# B115C.net
KiCad netlist of a schematic drawn in EAGLE
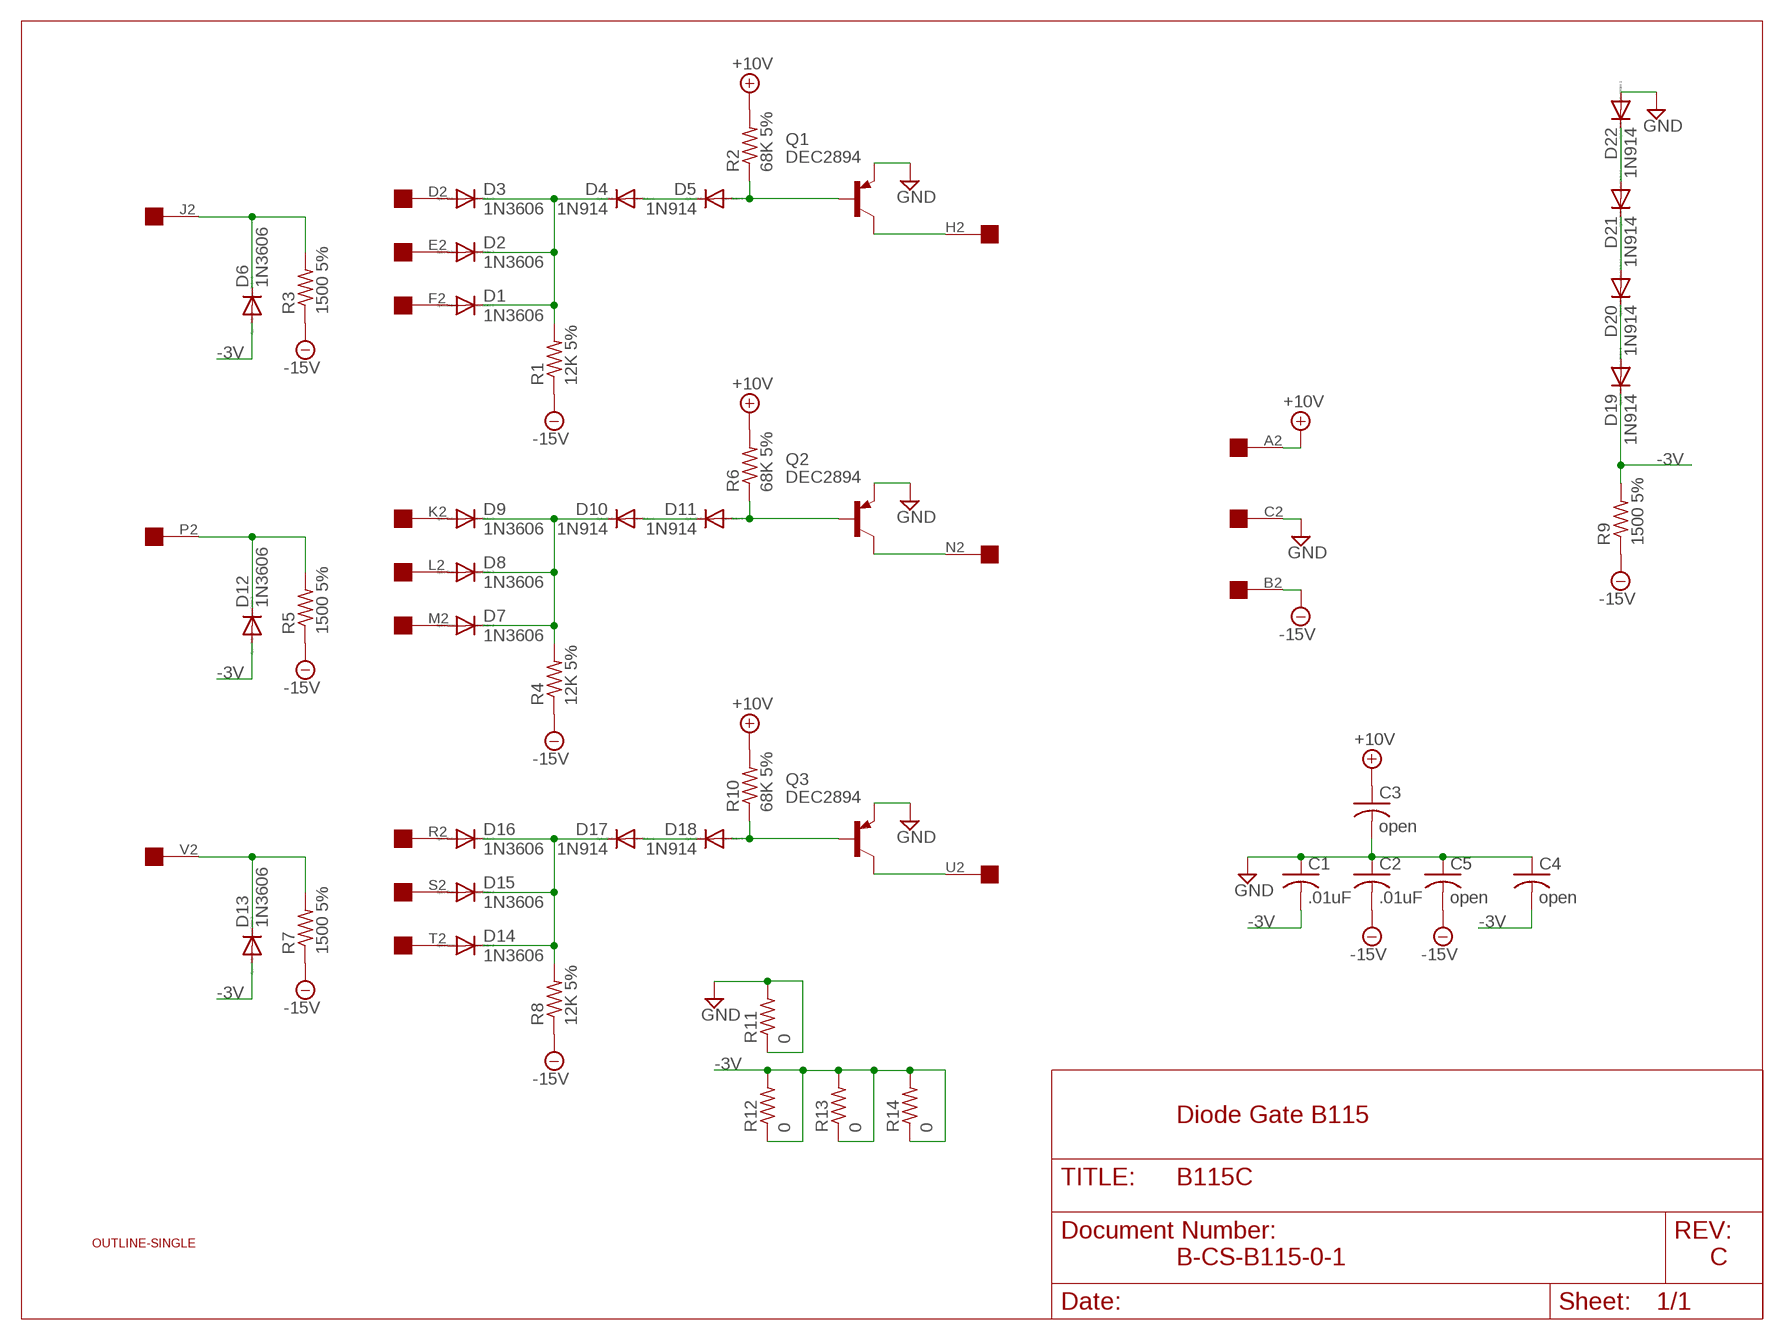
[diagram p0: schematic, sheet 1]

(export (version "E")
  (design (tool "Eeschema 10.0.6"))
  (components
    (comp (ref "C1")
      (value ".01uF")
      (footprint "eagle-import:C063-025X075")
      (libsource (lib "eagle-import") (part "C-US"))
    )
    (comp (ref "C2")
      (value ".01uF")
      (footprint "eagle-import:C063-025X075")
      (libsource (lib "eagle-import") (part "C-US"))
    )
    (comp (ref "C3")
      (value "open")
      (footprint "eagle-import:C063-025X075")
      (libsource (lib "eagle-import") (part "C-US"))
    )
    (comp (ref "C4")
      (value "open")
      (footprint "eagle-import:C063-025X075")
      (libsource (lib "eagle-import") (part "C-US"))
    )
    (comp (ref "C5")
      (value "open")
      (footprint "eagle-import:C063-025X075")
      (libsource (lib "eagle-import") (part "C-US"))
    )
    (comp (ref "D1")
      (value "1N3606")
      (footprint "eagle-import:DO35-10")
      (libsource (lib "eagle-import") (part "1N4148DO35-10"))
    )
    (comp (ref "D2")
      (value "1N3606")
      (footprint "eagle-import:DO35-10")
      (libsource (lib "eagle-import") (part "1N4148DO35-10"))
    )
    (comp (ref "D3")
      (value "1N3606")
      (footprint "eagle-import:DO35-10")
      (libsource (lib "eagle-import") (part "1N4148DO35-10"))
    )
    (comp (ref "D4")
      (value "1N914")
      (footprint "eagle-import:DO35-10")
      (libsource (lib "eagle-import") (part "1N4148DO35-10"))
    )
    (comp (ref "D5")
      (value "1N914")
      (footprint "eagle-import:DO35-10")
      (libsource (lib "eagle-import") (part "1N4148DO35-10"))
    )
    (comp (ref "D6")
      (value "1N3606")
      (footprint "eagle-import:DO35-10")
      (libsource (lib "eagle-import") (part "1N4148DO35-10"))
    )
    (comp (ref "D7")
      (value "1N3606")
      (footprint "eagle-import:DO35-10")
      (libsource (lib "eagle-import") (part "1N4148DO35-10"))
    )
    (comp (ref "D8")
      (value "1N3606")
      (footprint "eagle-import:DO35-10")
      (libsource (lib "eagle-import") (part "1N4148DO35-10"))
    )
    (comp (ref "D9")
      (value "1N3606")
      (footprint "eagle-import:DO35-10")
      (libsource (lib "eagle-import") (part "1N4148DO35-10"))
    )
    (comp (ref "D10")
      (value "1N914")
      (footprint "eagle-import:DO35-10")
      (libsource (lib "eagle-import") (part "1N4148DO35-10"))
    )
    (comp (ref "D11")
      (value "1N914")
      (footprint "eagle-import:DO35-10")
      (libsource (lib "eagle-import") (part "1N4148DO35-10"))
    )
    (comp (ref "D12")
      (value "1N3606")
      (footprint "eagle-import:DO35-10")
      (libsource (lib "eagle-import") (part "1N4148DO35-10"))
    )
    (comp (ref "D13")
      (value "1N3606")
      (footprint "eagle-import:DO35-10")
      (libsource (lib "eagle-import") (part "1N4148DO35-10"))
    )
    (comp (ref "D14")
      (value "1N3606")
      (footprint "eagle-import:DO35-10")
      (libsource (lib "eagle-import") (part "1N4148DO35-10"))
    )
    (comp (ref "D15")
      (value "1N3606")
      (footprint "eagle-import:DO35-10")
      (libsource (lib "eagle-import") (part "1N4148DO35-10"))
    )
    (comp (ref "D16")
      (value "1N3606")
      (footprint "eagle-import:DO35-10")
      (libsource (lib "eagle-import") (part "1N4148DO35-10"))
    )
    (comp (ref "D17")
      (value "1N914")
      (footprint "eagle-import:DO35-10")
      (libsource (lib "eagle-import") (part "1N4148DO35-10"))
    )
    (comp (ref "D18")
      (value "1N914")
      (footprint "eagle-import:DO35-10")
      (libsource (lib "eagle-import") (part "1N4148DO35-10"))
    )
    (comp (ref "D19")
      (value "1N914")
      (footprint "eagle-import:DO35-10")
      (libsource (lib "eagle-import") (part "1N4148DO35-10"))
    )
    (comp (ref "D20")
      (value "1N914")
      (footprint "eagle-import:DO35-10")
      (libsource (lib "eagle-import") (part "1N4148DO35-10"))
    )
    (comp (ref "D21")
      (value "1N914")
      (footprint "eagle-import:DO35-10")
      (libsource (lib "eagle-import") (part "1N4148DO35-10"))
    )
    (comp (ref "D22")
      (value "1N914")
      (footprint "eagle-import:DO35-10")
      (libsource (lib "eagle-import") (part "1N4148DO35-10"))
    )
    (comp (ref "Q1")
      (value "DEC2894")
      (footprint "eagle-import:TO39")
      (libsource (lib "eagle-import") (part "2N2904"))
    )
    (comp (ref "Q2")
      (value "DEC2894")
      (footprint "eagle-import:TO39")
      (libsource (lib "eagle-import") (part "2N2904"))
    )
    (comp (ref "Q3")
      (value "DEC2894")
      (footprint "eagle-import:TO39")
      (libsource (lib "eagle-import") (part "2N2904"))
    )
    (comp (ref "R1")
      (value "12K 5%")
      (footprint "eagle-import:0207_10")
      (libsource (lib "eagle-import") (part "R-US_0207/10"))
    )
    (comp (ref "R2")
      (value "68K 5%")
      (footprint "eagle-import:0207_10")
      (libsource (lib "eagle-import") (part "R-US_0207/10"))
    )
    (comp (ref "R3")
      (value "1500 5%")
      (footprint "eagle-import:0207_10")
      (libsource (lib "eagle-import") (part "R-US_0207/10"))
    )
    (comp (ref "R4")
      (value "12K 5%")
      (footprint "eagle-import:0207_10")
      (libsource (lib "eagle-import") (part "R-US_0207/10"))
    )
    (comp (ref "R5")
      (value "1500 5%")
      (footprint "eagle-import:0207_10")
      (libsource (lib "eagle-import") (part "R-US_0207/10"))
    )
    (comp (ref "R6")
      (value "68K 5%")
      (footprint "eagle-import:0207_10")
      (libsource (lib "eagle-import") (part "R-US_0207/10"))
    )
    (comp (ref "R7")
      (value "1500 5%")
      (footprint "eagle-import:0207_10")
      (libsource (lib "eagle-import") (part "R-US_0207/10"))
    )
    (comp (ref "R8")
      (value "12K 5%")
      (footprint "eagle-import:0207_10")
      (libsource (lib "eagle-import") (part "R-US_0207/10"))
    )
    (comp (ref "R9")
      (value "1500 5%")
      (footprint "eagle-import:0207_10")
      (libsource (lib "eagle-import") (part "R-US_0207/10"))
    )
    (comp (ref "R10")
      (value "68K 5%")
      (footprint "eagle-import:0207_10")
      (libsource (lib "eagle-import") (part "R-US_0207/10"))
    )
    (comp (ref "R11")
      (value "0")
      (footprint "eagle-import:0207_10")
      (libsource (lib "eagle-import") (part "R-US_0207/10"))
    )
    (comp (ref "R12")
      (value "0")
      (footprint "eagle-import:0207_10")
      (libsource (lib "eagle-import") (part "R-US_0207/10"))
    )
    (comp (ref "R13")
      (value "0")
      (footprint "eagle-import:0207_10")
      (libsource (lib "eagle-import") (part "R-US_0207/10"))
    )
    (comp (ref "R14")
      (value "0")
      (footprint "eagle-import:0207_10")
      (libsource (lib "eagle-import") (part "R-US_0207/10"))
    )
    (comp (ref "U$1")
      (value "OUTLINE-SINGLE")
      (footprint "eagle-import:SINGLE")
      (libsource (lib "eagle-import") (part "OUTLINE-SINGLE"))
    )
    (comp (ref "U$2")
      (value "EDGE-1")
      (footprint "eagle-import:EDGE-CON1")
      (libsource (lib "eagle-import") (part "EDGE-1"))
    )
  )
  (nets
    (net (code "1") (name "+10V") (class "Default")
      (node (ref "C3") (pin "1") (pinfunction "1_1") (pintype "passive"))
      (node (ref "R10") (pin "2") (pinfunction "2_2") (pintype "passive"))
      (node (ref "R2") (pin "2") (pinfunction "2_2") (pintype "passive"))
      (node (ref "R6") (pin "2") (pinfunction "2_2") (pintype "passive"))
      (node (ref "U$2") (pin "A2") (pinfunction "1_A2") (pintype "bidirectional"))
    )
    (net (code "2") (name "-15V") (class "Default")
      (node (ref "C2") (pin "2") (pinfunction "2_2") (pintype "passive"))
      (node (ref "C5") (pin "2") (pinfunction "2_2") (pintype "passive"))
      (node (ref "R1") (pin "1") (pinfunction "1_1") (pintype "passive"))
      (node (ref "R3") (pin "1") (pinfunction "1_1") (pintype "passive"))
      (node (ref "R4") (pin "1") (pinfunction "1_1") (pintype "passive"))
      (node (ref "R5") (pin "1") (pinfunction "1_1") (pintype "passive"))
      (node (ref "R7") (pin "1") (pinfunction "1_1") (pintype "passive"))
      (node (ref "R8") (pin "1") (pinfunction "1_1") (pintype "passive"))
      (node (ref "R9") (pin "1") (pinfunction "1_1") (pintype "passive"))
      (node (ref "U$2") (pin "B2") (pinfunction "1_B2") (pintype "bidirectional"))
    )
    (net (code "3") (name "/-3V") (class "Default")
      (node (ref "C1") (pin "2") (pinfunction "2_2") (pintype "passive"))
      (node (ref "C4") (pin "2") (pinfunction "2_2") (pintype "passive"))
      (node (ref "D12") (pin "A") (pinfunction "A_A") (pintype "passive"))
      (node (ref "D13") (pin "A") (pinfunction "A_A") (pintype "passive"))
      (node (ref "D19") (pin "C") (pinfunction "C_C") (pintype "passive"))
      (node (ref "D6") (pin "A") (pinfunction "A_A") (pintype "passive"))
      (node (ref "R12") (pin "1") (pinfunction "1_1") (pintype "passive"))
      (node (ref "R12") (pin "2") (pinfunction "2_2") (pintype "passive"))
      (node (ref "R13") (pin "1") (pinfunction "1_1") (pintype "passive"))
      (node (ref "R13") (pin "2") (pinfunction "2_2") (pintype "passive"))
      (node (ref "R14") (pin "1") (pinfunction "1_1") (pintype "passive"))
      (node (ref "R14") (pin "2") (pinfunction "2_2") (pintype "passive"))
      (node (ref "R9") (pin "2") (pinfunction "2_2") (pintype "passive"))
    )
    (net (code "4") (name "GND") (class "Default")
      (node (ref "C1") (pin "1") (pinfunction "1_1") (pintype "passive"))
      (node (ref "C2") (pin "1") (pinfunction "1_1") (pintype "passive"))
      (node (ref "C3") (pin "2") (pinfunction "2_2") (pintype "passive"))
      (node (ref "C4") (pin "1") (pinfunction "1_1") (pintype "passive"))
      (node (ref "C5") (pin "1") (pinfunction "1_1") (pintype "passive"))
      (node (ref "D22") (pin "A") (pinfunction "A_A") (pintype "passive"))
      (node (ref "Q1") (pin "1") (pinfunction "E_1") (pintype "passive"))
      (node (ref "Q2") (pin "1") (pinfunction "E_1") (pintype "passive"))
      (node (ref "Q3") (pin "1") (pinfunction "E_1") (pintype "passive"))
      (node (ref "R11") (pin "1") (pinfunction "1_1") (pintype "passive"))
      (node (ref "R11") (pin "2") (pinfunction "2_2") (pintype "passive"))
      (node (ref "U$2") (pin "C2") (pinfunction "1_C2") (pintype "bidirectional"))
    )
    (net (code "5") (name "Net-(D1-PadC)") (class "Default")
      (node (ref "D1") (pin "C") (pinfunction "C_C") (pintype "passive"))
      (node (ref "D2") (pin "C") (pinfunction "C_C") (pintype "passive"))
      (node (ref "D3") (pin "C") (pinfunction "C_C") (pintype "passive"))
      (node (ref "D4") (pin "C") (pinfunction "C_C") (pintype "passive"))
      (node (ref "R1") (pin "2") (pinfunction "2_2") (pintype "passive"))
    )
    (net (code "6") (name "Net-(D4-PadA)") (class "Default")
      (node (ref "D4") (pin "A") (pinfunction "A_A") (pintype "passive"))
      (node (ref "D5") (pin "C") (pinfunction "C_C") (pintype "passive"))
    )
    (net (code "7") (name "Net-(D10-PadA)") (class "Default")
      (node (ref "D10") (pin "A") (pinfunction "A_A") (pintype "passive"))
      (node (ref "D11") (pin "C") (pinfunction "C_C") (pintype "passive"))
    )
    (net (code "8") (name "Net-(D10-PadC)") (class "Default")
      (node (ref "D10") (pin "C") (pinfunction "C_C") (pintype "passive"))
      (node (ref "D7") (pin "C") (pinfunction "C_C") (pintype "passive"))
      (node (ref "D8") (pin "C") (pinfunction "C_C") (pintype "passive"))
      (node (ref "D9") (pin "C") (pinfunction "C_C") (pintype "passive"))
      (node (ref "R4") (pin "2") (pinfunction "2_2") (pintype "passive"))
    )
    (net (code "9") (name "Net-(D14-PadC)") (class "Default")
      (node (ref "D14") (pin "C") (pinfunction "C_C") (pintype "passive"))
      (node (ref "D15") (pin "C") (pinfunction "C_C") (pintype "passive"))
      (node (ref "D16") (pin "C") (pinfunction "C_C") (pintype "passive"))
      (node (ref "D17") (pin "C") (pinfunction "C_C") (pintype "passive"))
      (node (ref "R8") (pin "2") (pinfunction "2_2") (pintype "passive"))
    )
    (net (code "10") (name "Net-(D17-PadA)") (class "Default")
      (node (ref "D17") (pin "A") (pinfunction "A_A") (pintype "passive"))
      (node (ref "D18") (pin "C") (pinfunction "C_C") (pintype "passive"))
    )
    (net (code "11") (name "Net-(D19-PadA)") (class "Default")
      (node (ref "D19") (pin "A") (pinfunction "A_A") (pintype "passive"))
      (node (ref "D20") (pin "C") (pinfunction "C_C") (pintype "passive"))
    )
    (net (code "12") (name "Net-(D20-PadA)") (class "Default")
      (node (ref "D20") (pin "A") (pinfunction "A_A") (pintype "passive"))
      (node (ref "D21") (pin "C") (pinfunction "C_C") (pintype "passive"))
    )
    (net (code "13") (name "Net-(D21-PadA)") (class "Default")
      (node (ref "D21") (pin "A") (pinfunction "A_A") (pintype "passive"))
      (node (ref "D22") (pin "C") (pinfunction "C_C") (pintype "passive"))
    )
    (net (code "14") (name "Net-(Q1-B)") (class "Default")
      (node (ref "D5") (pin "A") (pinfunction "A_A") (pintype "passive"))
      (node (ref "Q1") (pin "2") (pinfunction "B_2") (pintype "passive"))
      (node (ref "R2") (pin "1") (pinfunction "1_1") (pintype "passive"))
    )
    (net (code "15") (name "Net-(Q1-C)") (class "Default")
      (node (ref "Q1") (pin "3") (pinfunction "C_3") (pintype "passive"))
      (node (ref "U$2") (pin "H2") (pinfunction "1_H2") (pintype "bidirectional"))
    )
    (net (code "16") (name "Net-(Q2-B)") (class "Default")
      (node (ref "D11") (pin "A") (pinfunction "A_A") (pintype "passive"))
      (node (ref "Q2") (pin "2") (pinfunction "B_2") (pintype "passive"))
      (node (ref "R6") (pin "1") (pinfunction "1_1") (pintype "passive"))
    )
    (net (code "17") (name "Net-(Q2-C)") (class "Default")
      (node (ref "Q2") (pin "3") (pinfunction "C_3") (pintype "passive"))
      (node (ref "U$2") (pin "N2") (pinfunction "1_N2") (pintype "bidirectional"))
    )
    (net (code "18") (name "Net-(Q3-B)") (class "Default")
      (node (ref "D18") (pin "A") (pinfunction "A_A") (pintype "passive"))
      (node (ref "Q3") (pin "2") (pinfunction "B_2") (pintype "passive"))
      (node (ref "R10") (pin "1") (pinfunction "1_1") (pintype "passive"))
    )
    (net (code "19") (name "Net-(Q3-C)") (class "Default")
      (node (ref "Q3") (pin "3") (pinfunction "C_3") (pintype "passive"))
      (node (ref "U$2") (pin "U2") (pinfunction "1_U2") (pintype "bidirectional"))
    )
    (net (code "20") (name "Net-(U$2D-1)") (class "Default")
      (node (ref "D3") (pin "A") (pinfunction "A_A") (pintype "passive"))
      (node (ref "U$2") (pin "D2") (pinfunction "1_D2") (pintype "bidirectional"))
    )
    (net (code "21") (name "Net-(U$2E-1)") (class "Default")
      (node (ref "D2") (pin "A") (pinfunction "A_A") (pintype "passive"))
      (node (ref "U$2") (pin "E2") (pinfunction "1_E2") (pintype "bidirectional"))
    )
    (net (code "22") (name "Net-(U$2F-1)") (class "Default")
      (node (ref "D1") (pin "A") (pinfunction "A_A") (pintype "passive"))
      (node (ref "U$2") (pin "F2") (pinfunction "1_F2") (pintype "bidirectional"))
    )
    (net (code "23") (name "Net-(U$2H-1)") (class "Default")
      (node (ref "D6") (pin "C") (pinfunction "C_C") (pintype "passive"))
      (node (ref "R3") (pin "2") (pinfunction "2_2") (pintype "passive"))
      (node (ref "U$2") (pin "J2") (pinfunction "1_J2") (pintype "bidirectional"))
    )
    (net (code "24") (name "Net-(U$2I-1)") (class "Default")
      (node (ref "D9") (pin "A") (pinfunction "A_A") (pintype "passive"))
      (node (ref "U$2") (pin "K2") (pinfunction "1_K2") (pintype "bidirectional"))
    )
    (net (code "25") (name "Net-(U$2J-1)") (class "Default")
      (node (ref "D8") (pin "A") (pinfunction "A_A") (pintype "passive"))
      (node (ref "U$2") (pin "L2") (pinfunction "1_L2") (pintype "bidirectional"))
    )
    (net (code "26") (name "Net-(U$2K-1)") (class "Default")
      (node (ref "D7") (pin "A") (pinfunction "A_A") (pintype "passive"))
      (node (ref "U$2") (pin "M2") (pinfunction "1_M2") (pintype "bidirectional"))
    )
    (net (code "27") (name "Net-(U$2M-1)") (class "Default")
      (node (ref "D12") (pin "C") (pinfunction "C_C") (pintype "passive"))
      (node (ref "R5") (pin "2") (pinfunction "2_2") (pintype "passive"))
      (node (ref "U$2") (pin "P2") (pinfunction "1_P2") (pintype "bidirectional"))
    )
    (net (code "28") (name "Net-(U$2N-1)") (class "Default")
      (node (ref "D16") (pin "A") (pinfunction "A_A") (pintype "passive"))
      (node (ref "U$2") (pin "R2") (pinfunction "1_R2") (pintype "bidirectional"))
    )
    (net (code "29") (name "Net-(U$2O-1)") (class "Default")
      (node (ref "D15") (pin "A") (pinfunction "A_A") (pintype "passive"))
      (node (ref "U$2") (pin "S2") (pinfunction "1_S2") (pintype "bidirectional"))
    )
    (net (code "30") (name "Net-(U$2P-1)") (class "Default")
      (node (ref "D14") (pin "A") (pinfunction "A_A") (pintype "passive"))
      (node (ref "U$2") (pin "T2") (pinfunction "1_T2") (pintype "bidirectional"))
    )
    (net (code "31") (name "Net-(U$2R-1)") (class "Default")
      (node (ref "D13") (pin "C") (pinfunction "C_C") (pintype "passive"))
      (node (ref "R7") (pin "2") (pinfunction "2_2") (pintype "passive"))
      (node (ref "U$2") (pin "V2") (pinfunction "1_V2") (pintype "bidirectional"))
    )
  )
)
